# Dual_supply_adi.net
KiCad netlist of a schematic drawn in EAGLE
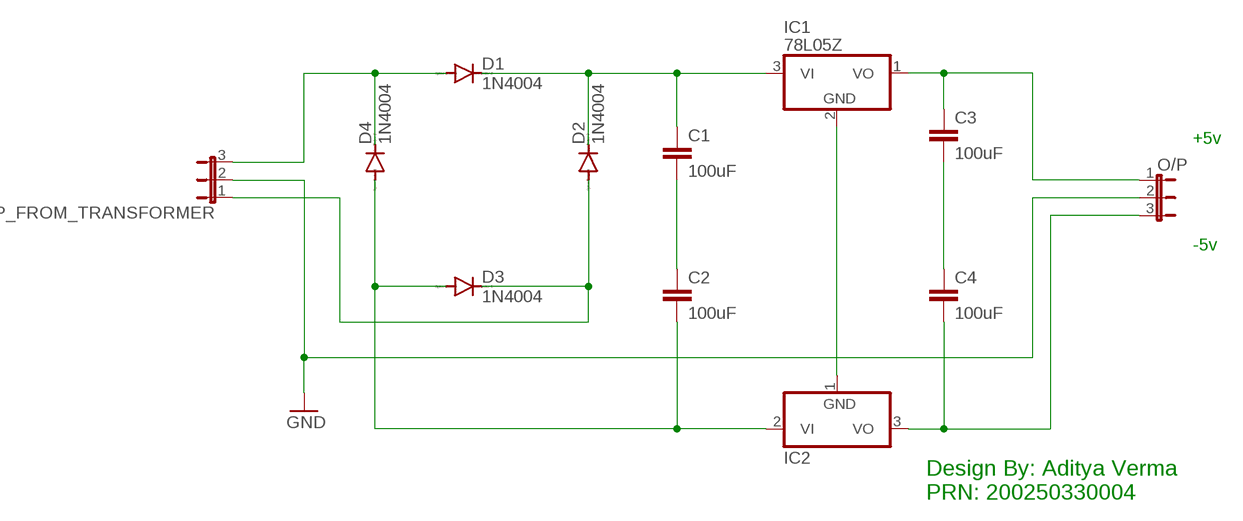
[diagram p0: schematic, sheet 1]

(export (version "E")
  (design (tool "Eeschema 10.0.6"))
  (components
    (comp (ref "C1")
      (value "100uF")
      (footprint "eagle-import:C2.5-3")
      (libsource (lib "eagle-import") (part "C2,5-3"))
    )
    (comp (ref "C2")
      (value "100uF")
      (footprint "eagle-import:C2.5-3")
      (libsource (lib "eagle-import") (part "C2,5-3"))
    )
    (comp (ref "C3")
      (value "100uF")
      (footprint "eagle-import:C2.5-3")
      (libsource (lib "eagle-import") (part "C2,5-3"))
    )
    (comp (ref "C4")
      (value "100uF")
      (footprint "eagle-import:C2.5-3")
      (libsource (lib "eagle-import") (part "C2,5-3"))
    )
    (comp (ref "D1")
      (value "1N4004")
      (footprint "eagle-import:DO41-10")
      (libsource (lib "eagle-import") (part "1N4004"))
    )
    (comp (ref "D2")
      (value "1N4004")
      (footprint "eagle-import:DO41-10")
      (libsource (lib "eagle-import") (part "1N4004"))
    )
    (comp (ref "D3")
      (value "1N4004")
      (footprint "eagle-import:DO41-10")
      (libsource (lib "eagle-import") (part "1N4004"))
    )
    (comp (ref "D4")
      (value "1N4004")
      (footprint "eagle-import:DO41-10")
      (libsource (lib "eagle-import") (part "1N4004"))
    )
    (comp (ref "I/P_FROM_TRANSFORMER")
      (value "JP2E")
      (footprint "eagle-import:JP2")
      (libsource (lib "eagle-import") (part "JP2E"))
    )
    (comp (ref "IC1")
      (value "78L05Z")
      (footprint "eagle-import:TO92")
      (libsource (lib "eagle-import") (part "78ZL05"))
    )
    (comp (ref "IC2")
      (value "79L05Z")
      (footprint "eagle-import:TO92")
      (libsource (lib "eagle-import") (part "79ZL05"))
    )
    (comp (ref "O/P")
      (value "JP2E")
      (footprint "eagle-import:JP2")
      (libsource (lib "eagle-import") (part "JP2E"))
    )
  )
  (nets
    (net (code "1") (name "GND") (class "Default")
      (node (ref "I/P_FROM_TRANSFORMER") (pin "2") (pinfunction "2_2") (pintype "passive"))
      (node (ref "O/P") (pin "2") (pinfunction "2_2") (pintype "passive"))
    )
    (net (code "2") (name "Net-(C1-Pad2)") (class "Default")
      (node (ref "C1") (pin "2") (pinfunction "2_2") (pintype "passive"))
      (node (ref "C2") (pin "1") (pinfunction "1_1") (pintype "passive"))
    )
    (net (code "3") (name "Net-(C3-Pad2)") (class "Default")
      (node (ref "C3") (pin "2") (pinfunction "2_2") (pintype "passive"))
      (node (ref "C4") (pin "1") (pinfunction "1_1") (pintype "passive"))
    )
    (net (code "4") (name "Net-(D1-PadA)") (class "Default")
      (node (ref "D1") (pin "A") (pinfunction "A_A") (pintype "passive"))
      (node (ref "D4") (pin "C") (pinfunction "C_C") (pintype "passive"))
      (node (ref "I/P_FROM_TRANSFORMER") (pin "3") (pinfunction "3_3") (pintype "passive"))
    )
    (net (code "5") (name "Net-(D2-PadA)") (class "Default")
      (node (ref "D2") (pin "A") (pinfunction "A_A") (pintype "passive"))
      (node (ref "D3") (pin "C") (pinfunction "C_C") (pintype "passive"))
      (node (ref "I/P_FROM_TRANSFORMER") (pin "1") (pinfunction "1_1") (pintype "passive"))
    )
    (net (code "6") (name "Net-(IC1-GND)") (class "Default")
      (node (ref "IC1") (pin "2") (pinfunction "GND_2") (pintype "passive"))
      (node (ref "IC2") (pin "1") (pinfunction "GND_1") (pintype "passive"))
    )
    (net (code "7") (name "Net-(IC1-VI)") (class "Default")
      (node (ref "C1") (pin "1") (pinfunction "1_1") (pintype "passive"))
      (node (ref "D1") (pin "C") (pinfunction "C_C") (pintype "passive"))
      (node (ref "D2") (pin "C") (pinfunction "C_C") (pintype "passive"))
      (node (ref "IC1") (pin "3") (pinfunction "VI_3") (pintype "input"))
    )
    (net (code "8") (name "Net-(IC1-VO)") (class "Default")
      (node (ref "C3") (pin "1") (pinfunction "1_1") (pintype "passive"))
      (node (ref "IC1") (pin "1") (pinfunction "VO_1") (pintype "passive"))
      (node (ref "O/P") (pin "1") (pinfunction "1_1") (pintype "passive"))
    )
    (net (code "9") (name "Net-(IC2-VI)") (class "Default")
      (node (ref "C2") (pin "2") (pinfunction "2_2") (pintype "passive"))
      (node (ref "D3") (pin "A") (pinfunction "A_A") (pintype "passive"))
      (node (ref "D4") (pin "A") (pinfunction "A_A") (pintype "passive"))
      (node (ref "IC2") (pin "2") (pinfunction "VI_2") (pintype "input"))
    )
    (net (code "10") (name "Net-(IC2-VO)") (class "Default")
      (node (ref "C4") (pin "2") (pinfunction "2_2") (pintype "passive"))
      (node (ref "IC2") (pin "3") (pinfunction "VO_3") (pintype "passive"))
      (node (ref "O/P") (pin "3") (pinfunction "3_3") (pintype "passive"))
    )
  )
)
